# teensy_toslink_v1_2.net
KiCad netlist of a schematic drawn in EAGLE
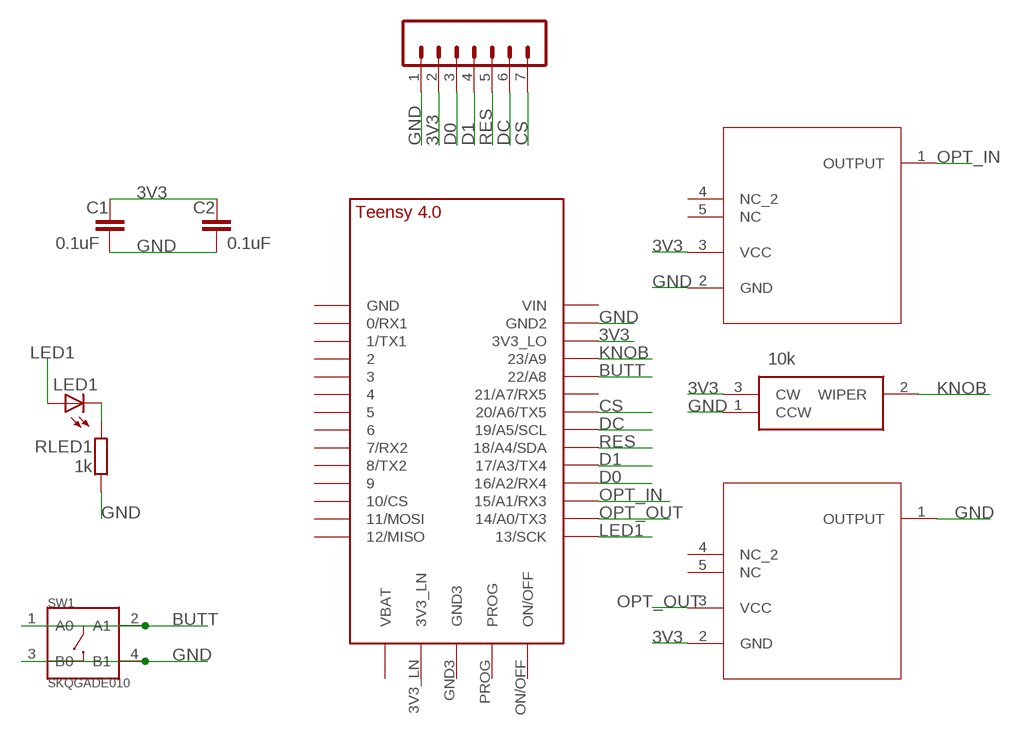
[diagram p0: schematic, sheet 1]

(export (version "E")
  (design (tool "Eeschema 10.0.6"))
  (components
    (comp (ref "C1")
      (value "0.1uF")
      (footprint "eagle-import:C0805")
      (libsource (lib "eagle-import") (part "C-EUC0805"))
    )
    (comp (ref "C2")
      (value "0.1uF")
      (footprint "eagle-import:C0805")
      (libsource (lib "eagle-import") (part "C-EUC0805"))
    )
    (comp (ref "CN1")
      (value "8p-2.54")
      (footprint "eagle-import:1X07")
      (libsource (lib "eagle-import") (part "CONN_07"))
    )
    (comp (ref "J1")
      (value "TORX141P(F)TORX141P(F)_TOS")
      (footprint "eagle-import:TORX141P(F)_TOS")
      (fields
        (field (name "MANUFACTURER_PART_NUMBER") "TORX141P(F)")
        (field (name "COPYRIGHT") "Copyright (C) 2023 Ultra Librarian. All rights reserved.")
      )
      (libsource (lib "eagle-import") (part "TORX141P(F)TORX141P(F)_TOS"))
    )
    (comp (ref "J2")
      (value "TORX141P(F)TORX141P(F)_TOS")
      (footprint "eagle-import:TORX141P(F)_TOS")
      (fields
        (field (name "MANUFACTURER_PART_NUMBER") "TORX141P(F)")
        (field (name "COPYRIGHT") "Copyright (C) 2023 Ultra Librarian. All rights reserved.")
      )
      (libsource (lib "eagle-import") (part "TORX141P(F)TORX141P(F)_TOS"))
    )
    (comp (ref "LED1")
      (value "0805")
      (footprint "eagle-import:CHIPLED_0805")
      (libsource (lib "eagle-import") (part "LEDCHIPLED_0805"))
    )
    (comp (ref "RLED1")
      (value "1k")
      (footprint "eagle-import:R0805")
      (libsource (lib "eagle-import") (part "R-EU_R0805"))
    )
    (comp (ref "SW1")
      (value "SKQGADE010")
      (footprint "eagle-import:SW4-SMD-5.2X5.2X1.5MM")
      (libsource (lib "eagle-import") (part "SMD-BUTTON(4P-5.2X5.2X1.5MM-SKQGADE010)-SKQGADE010"))
    )
    (comp (ref "U$1")
      (value "TEENSY_4.0")
      (footprint "eagle-import:TEENSY_4.0")
      (libsource (lib "eagle-import") (part "TEENSY_4.0"))
    )
    (comp (ref "VR1")
      (value "10k")
      (footprint "eagle-import:3386P1103TLF")
      (fields
        (field (name "MANUFACTURER_PART_NUMBER") "3386P-1-103")
        (field (name "MOUSER_PART_NUMBER") "652-3386P-1-103")
      )
      (libsource (lib "eagle-import") (part "3386P-1-103"))
    )
  )
  (nets
    (net (code "1") (name "/3V3") (class "Default")
      (node (ref "C1") (pin "1") (pinfunction "1_1") (pintype "passive"))
      (node (ref "C2") (pin "1") (pinfunction "1_1") (pintype "passive"))
      (node (ref "CN1") (pin "2") (pinfunction "2_2") (pintype "passive"))
      (node (ref "J1") (pin "3") (pinfunction "VCC_3") (pintype "power_in"))
      (node (ref "J2") (pin "2") (pinfunction "GND_2") (pintype "passive"))
      (node (ref "U$1") (pin "3V3_LO") (pinfunction "3V3_LO_3V3_LO") (pintype "bidirectional"))
      (node (ref "VR1") (pin "3") (pinfunction "CW_3") (pintype "bidirectional"))
    )
    (net (code "2") (name "/BUTT") (class "Default")
      (node (ref "SW1") (pin "1") (pinfunction "A0_1") (pintype "bidirectional"))
      (node (ref "SW1") (pin "2") (pinfunction "A1_2") (pintype "bidirectional"))
      (node (ref "U$1") (pin "22/A8") (pinfunction "22/A8_22/A8") (pintype "bidirectional"))
    )
    (net (code "3") (name "/CS") (class "Default")
      (node (ref "CN1") (pin "7") (pinfunction "7_7") (pintype "passive"))
      (node (ref "U$1") (pin "20/A6") (pinfunction "20/A6/TX5_20/A6") (pintype "bidirectional"))
    )
    (net (code "4") (name "/D0") (class "Default")
      (node (ref "CN1") (pin "3") (pinfunction "3_3") (pintype "passive"))
      (node (ref "U$1") (pin "16/A2") (pinfunction "16/A2/RX4_16/A2") (pintype "bidirectional"))
    )
    (net (code "5") (name "/D1") (class "Default")
      (node (ref "CN1") (pin "4") (pinfunction "4_4") (pintype "passive"))
      (node (ref "U$1") (pin "17/A3") (pinfunction "17/A3/TX4_17/A3") (pintype "bidirectional"))
    )
    (net (code "6") (name "/DC") (class "Default")
      (node (ref "CN1") (pin "6") (pinfunction "6_6") (pintype "passive"))
      (node (ref "U$1") (pin "19/A5/SCL") (pinfunction "19/A5/SCL_19/A5/SCL") (pintype "bidirectional"))
    )
    (net (code "7") (name "/GND") (class "Default")
      (node (ref "C1") (pin "2") (pinfunction "2_2") (pintype "passive"))
      (node (ref "C2") (pin "2") (pinfunction "2_2") (pintype "passive"))
      (node (ref "CN1") (pin "1") (pinfunction "1_1") (pintype "passive"))
      (node (ref "J1") (pin "2") (pinfunction "GND_2") (pintype "passive"))
      (node (ref "J2") (pin "1") (pinfunction "OUTPUT_1") (pintype "output"))
      (node (ref "RLED1") (pin "1") (pinfunction "1_1") (pintype "passive"))
      (node (ref "SW1") (pin "3") (pinfunction "B0_3") (pintype "bidirectional"))
      (node (ref "SW1") (pin "4") (pinfunction "B1_4") (pintype "bidirectional"))
      (node (ref "U$1") (pin "GND2") (pinfunction "GND2_GND2") (pintype "bidirectional"))
      (node (ref "VR1") (pin "1") (pinfunction "CCW_1") (pintype "bidirectional"))
    )
    (net (code "8") (name "/KNOB") (class "Default")
      (node (ref "U$1") (pin "23/A9") (pinfunction "23/A9_23/A9") (pintype "bidirectional"))
      (node (ref "VR1") (pin "2") (pinfunction "WIPER_2") (pintype "bidirectional"))
    )
    (net (code "9") (name "/LED1") (class "Default")
      (node (ref "LED1") (pin "A") (pinfunction "A_A") (pintype "passive"))
      (node (ref "U$1") (pin "13/SCK") (pinfunction "13/SCK_13/SCK") (pintype "bidirectional"))
    )
    (net (code "10") (name "/OPT_IN") (class "Default")
      (node (ref "J1") (pin "1") (pinfunction "OUTPUT_1") (pintype "output"))
      (node (ref "U$1") (pin "15/A1") (pinfunction "15/A1/RX3_15/A1") (pintype "bidirectional"))
    )
    (net (code "11") (name "/OPT_OUT") (class "Default")
      (node (ref "J2") (pin "3") (pinfunction "VCC_3") (pintype "power_in"))
      (node (ref "U$1") (pin "14/A0") (pinfunction "14/A0/TX3_14/A0") (pintype "bidirectional"))
    )
    (net (code "12") (name "/RES") (class "Default")
      (node (ref "CN1") (pin "5") (pinfunction "5_5") (pintype "passive"))
      (node (ref "U$1") (pin "18/A4/SDA") (pinfunction "18/A4/SDA_18/A4/SDA") (pintype "bidirectional"))
    )
    (net (code "13") (name "Net-(LED1-PadC)") (class "Default")
      (node (ref "LED1") (pin "C") (pinfunction "C_C") (pintype "passive"))
      (node (ref "RLED1") (pin "2") (pinfunction "2_2") (pintype "passive"))
    )
    (net (code "14") (name "unconnected-(J1-NC-Pad5)") (class "Default")
      (node (ref "J1") (pin "5") (pinfunction "NC_5") (pintype "no_connect"))
    )
    (net (code "15") (name "unconnected-(J1-NC_2-Pad4)") (class "Default")
      (node (ref "J1") (pin "4") (pinfunction "NC_2_4") (pintype "no_connect"))
    )
    (net (code "16") (name "unconnected-(J2-NC-Pad5)") (class "Default")
      (node (ref "J2") (pin "5") (pinfunction "NC_5") (pintype "no_connect"))
    )
    (net (code "17") (name "unconnected-(J2-NC_2-Pad4)") (class "Default")
      (node (ref "J2") (pin "4") (pinfunction "NC_2_4") (pintype "no_connect"))
    )
    (net (code "18") (name "unconnected-(U$1-0{slash}RX1-Pad0{slash}RX)") (class "Default")
      (node (ref "U$1") (pin "0/RX") (pinfunction "0/RX1_0/RX") (pintype "bidirectional"))
    )
    (net (code "19") (name "unconnected-(U$1-1{slash}TX1-Pad1{slash}TX)") (class "Default")
      (node (ref "U$1") (pin "1/TX") (pinfunction "1/TX1_1/TX") (pintype "bidirectional"))
    )
    (net (code "20") (name "unconnected-(U$1-3-Pad3{slash}CANTX)") (class "Default")
      (node (ref "U$1") (pin "3/CANTX") (pinfunction "3_3/CANTX") (pintype "bidirectional"))
    )
    (net (code "21") (name "unconnected-(U$1-4-Pad4{slash}CANRX)") (class "Default")
      (node (ref "U$1") (pin "4/CANRX") (pinfunction "4_4/CANRX") (pintype "bidirectional"))
    )
    (net (code "22") (name "unconnected-(U$1-7{slash}RX2-Pad7)") (class "Default")
      (node (ref "U$1") (pin "7") (pinfunction "7/RX2_7") (pintype "bidirectional"))
    )
    (net (code "23") (name "unconnected-(U$1-8{slash}TX2-Pad8)") (class "Default")
      (node (ref "U$1") (pin "8") (pinfunction "8/TX2_8") (pintype "bidirectional"))
    )
    (net (code "24") (name "unconnected-(U$1-9-Pad9{slash}CS)") (class "Default")
      (node (ref "U$1") (pin "9/CS") (pinfunction "9_9/CS") (pintype "bidirectional"))
    )
    (net (code "25") (name "unconnected-(U$1-21{slash}A7{slash}RX5-Pad21{slash}A7)") (class "Default")
      (node (ref "U$1") (pin "21/A7") (pinfunction "21/A7/RX5_21/A7") (pintype "bidirectional"))
    )
    (net (code "26") (name "unconnected-(U$1-Pad2)") (class "Default")
      (node (ref "U$1") (pin "2") (pinfunction "2_2") (pintype "bidirectional"))
    )
    (net (code "27") (name "unconnected-(U$1-Pad3V3_LN)") (class "Default")
      (node (ref "U$1") (pin "3V3_LN") (pinfunction "3V3_LN_3V3_LN") (pintype "bidirectional"))
    )
    (net (code "28") (name "unconnected-(U$1-Pad5)") (class "Default")
      (node (ref "U$1") (pin "5") (pinfunction "5_5") (pintype "bidirectional"))
    )
    (net (code "29") (name "unconnected-(U$1-Pad6)") (class "Default")
      (node (ref "U$1") (pin "6") (pinfunction "6_6") (pintype "bidirectional"))
    )
    (net (code "30") (name "unconnected-(U$1-Pad10{slash}CS)") (class "Default")
      (node (ref "U$1") (pin "10/CS") (pinfunction "10/CS_10/CS") (pintype "bidirectional"))
    )
    (net (code "31") (name "unconnected-(U$1-Pad11{slash}MOSI)") (class "Default")
      (node (ref "U$1") (pin "11/MOSI") (pinfunction "11/MOSI_11/MOSI") (pintype "bidirectional"))
    )
    (net (code "32") (name "unconnected-(U$1-Pad12{slash}MISO)") (class "Default")
      (node (ref "U$1") (pin "12/MISO") (pinfunction "12/MISO_12/MISO") (pintype "bidirectional"))
    )
    (net (code "33") (name "unconnected-(U$1-PadGND)") (class "Default")
      (node (ref "U$1") (pin "GND") (pinfunction "GND_GND") (pintype "bidirectional"))
    )
    (net (code "34") (name "unconnected-(U$1-PadGND3)") (class "Default")
      (node (ref "U$1") (pin "GND3") (pinfunction "GND3_GND3") (pintype "bidirectional"))
    )
    (net (code "35") (name "unconnected-(U$1-PadON{slash}OFF)") (class "Default")
      (node (ref "U$1") (pin "ON/OFF") (pinfunction "ON/OFF_ON/OFF") (pintype "bidirectional"))
    )
    (net (code "36") (name "unconnected-(U$1-PadPROG)") (class "Default")
      (node (ref "U$1") (pin "PROG") (pinfunction "PROG_PROG") (pintype "bidirectional"))
    )
    (net (code "37") (name "unconnected-(U$1-PadVIN)") (class "Default")
      (node (ref "U$1") (pin "VIN") (pinfunction "VIN_VIN") (pintype "bidirectional"))
    )
    (net (code "38") (name "unconnected-(U$1-VBAT-PadVBAT\\)") (class "Default")
      (node (ref "U$1") (pin "VBAT\\") (pinfunction "VBAT_VBAT\\") (pintype "bidirectional"))
    )
  )
)
